# design-v1_1.net
KiCad netlist of a schematic drawn in EAGLE
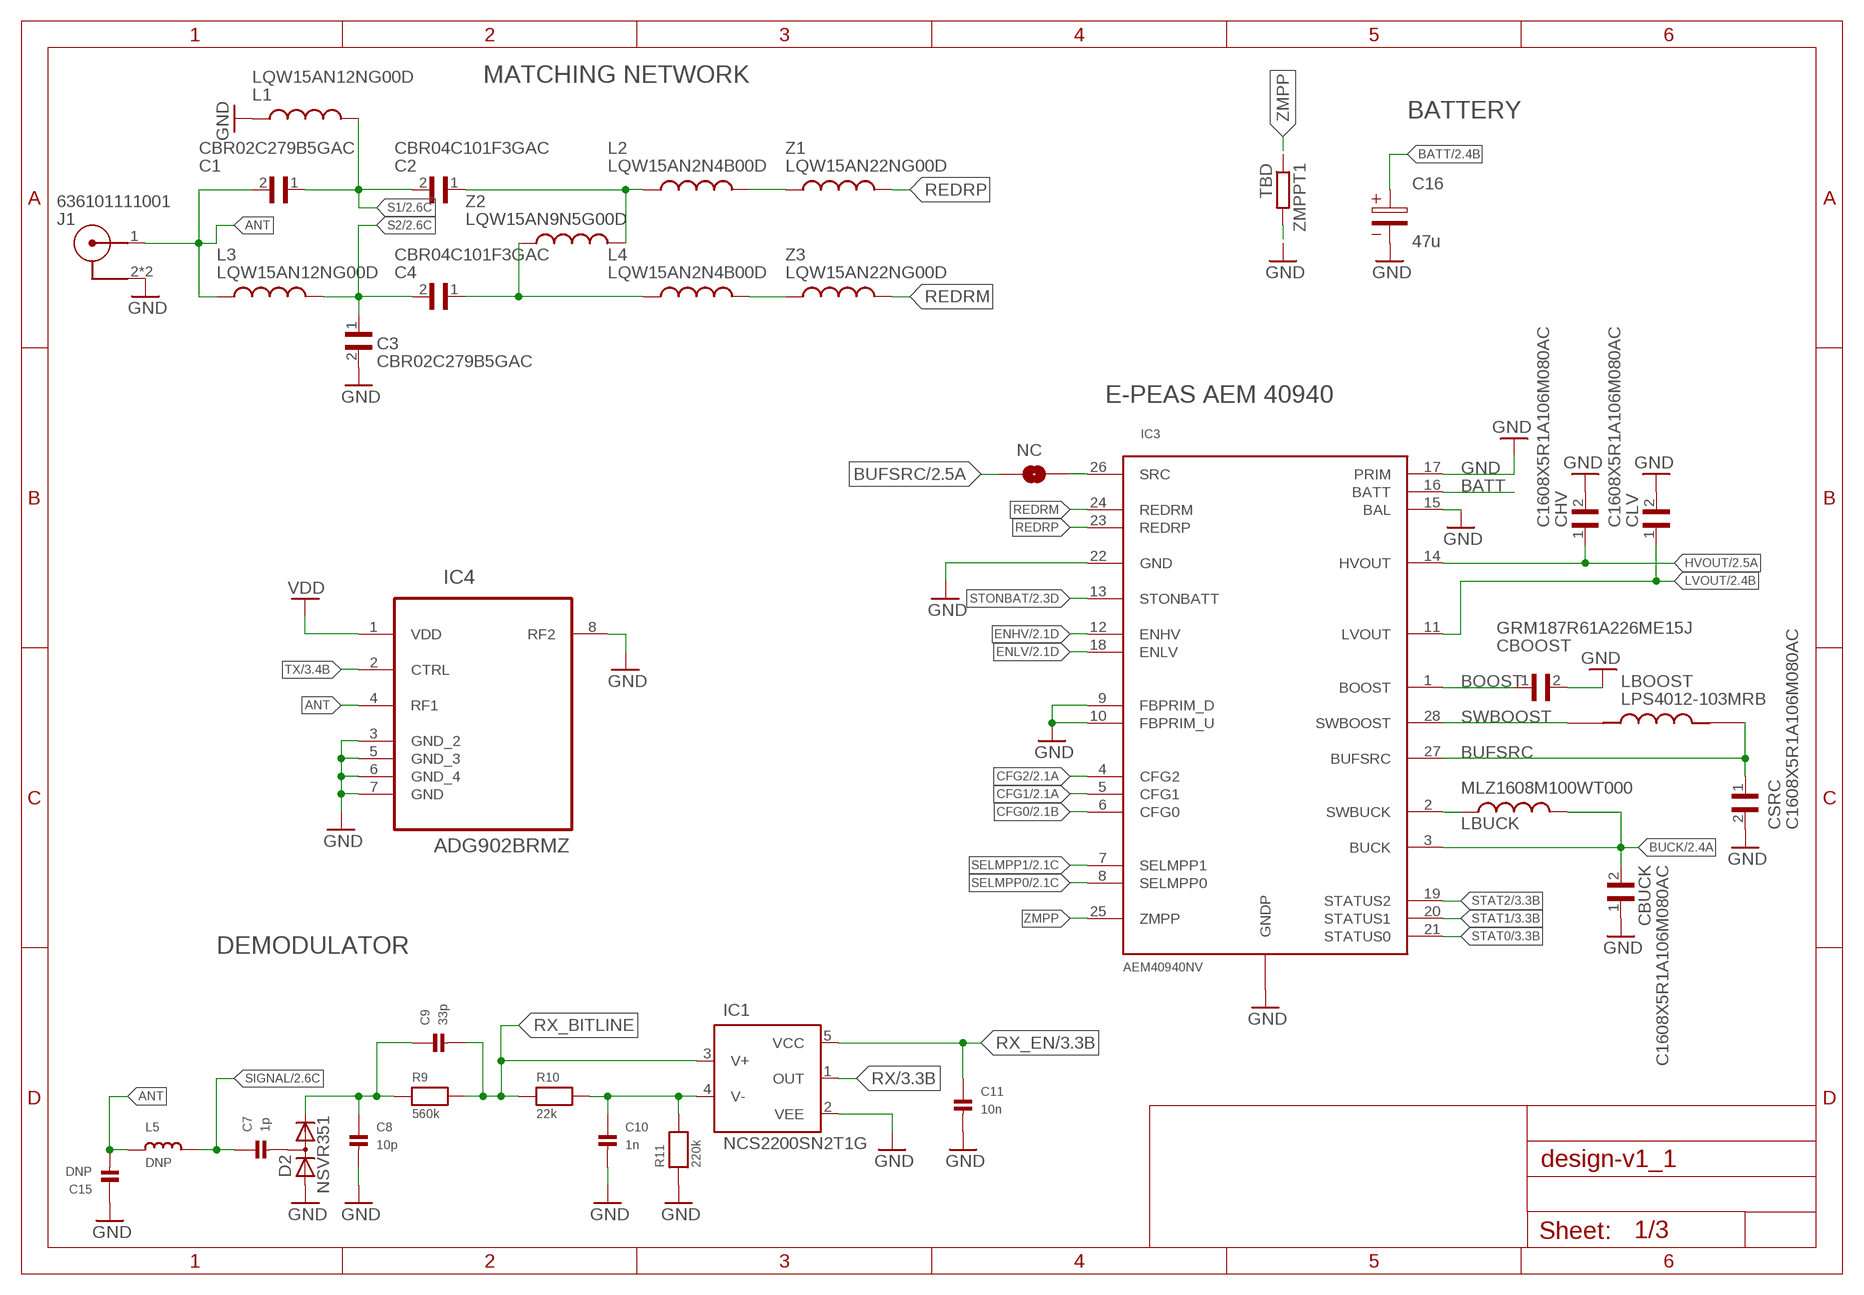
[diagram p0: schematic, sheet 1]
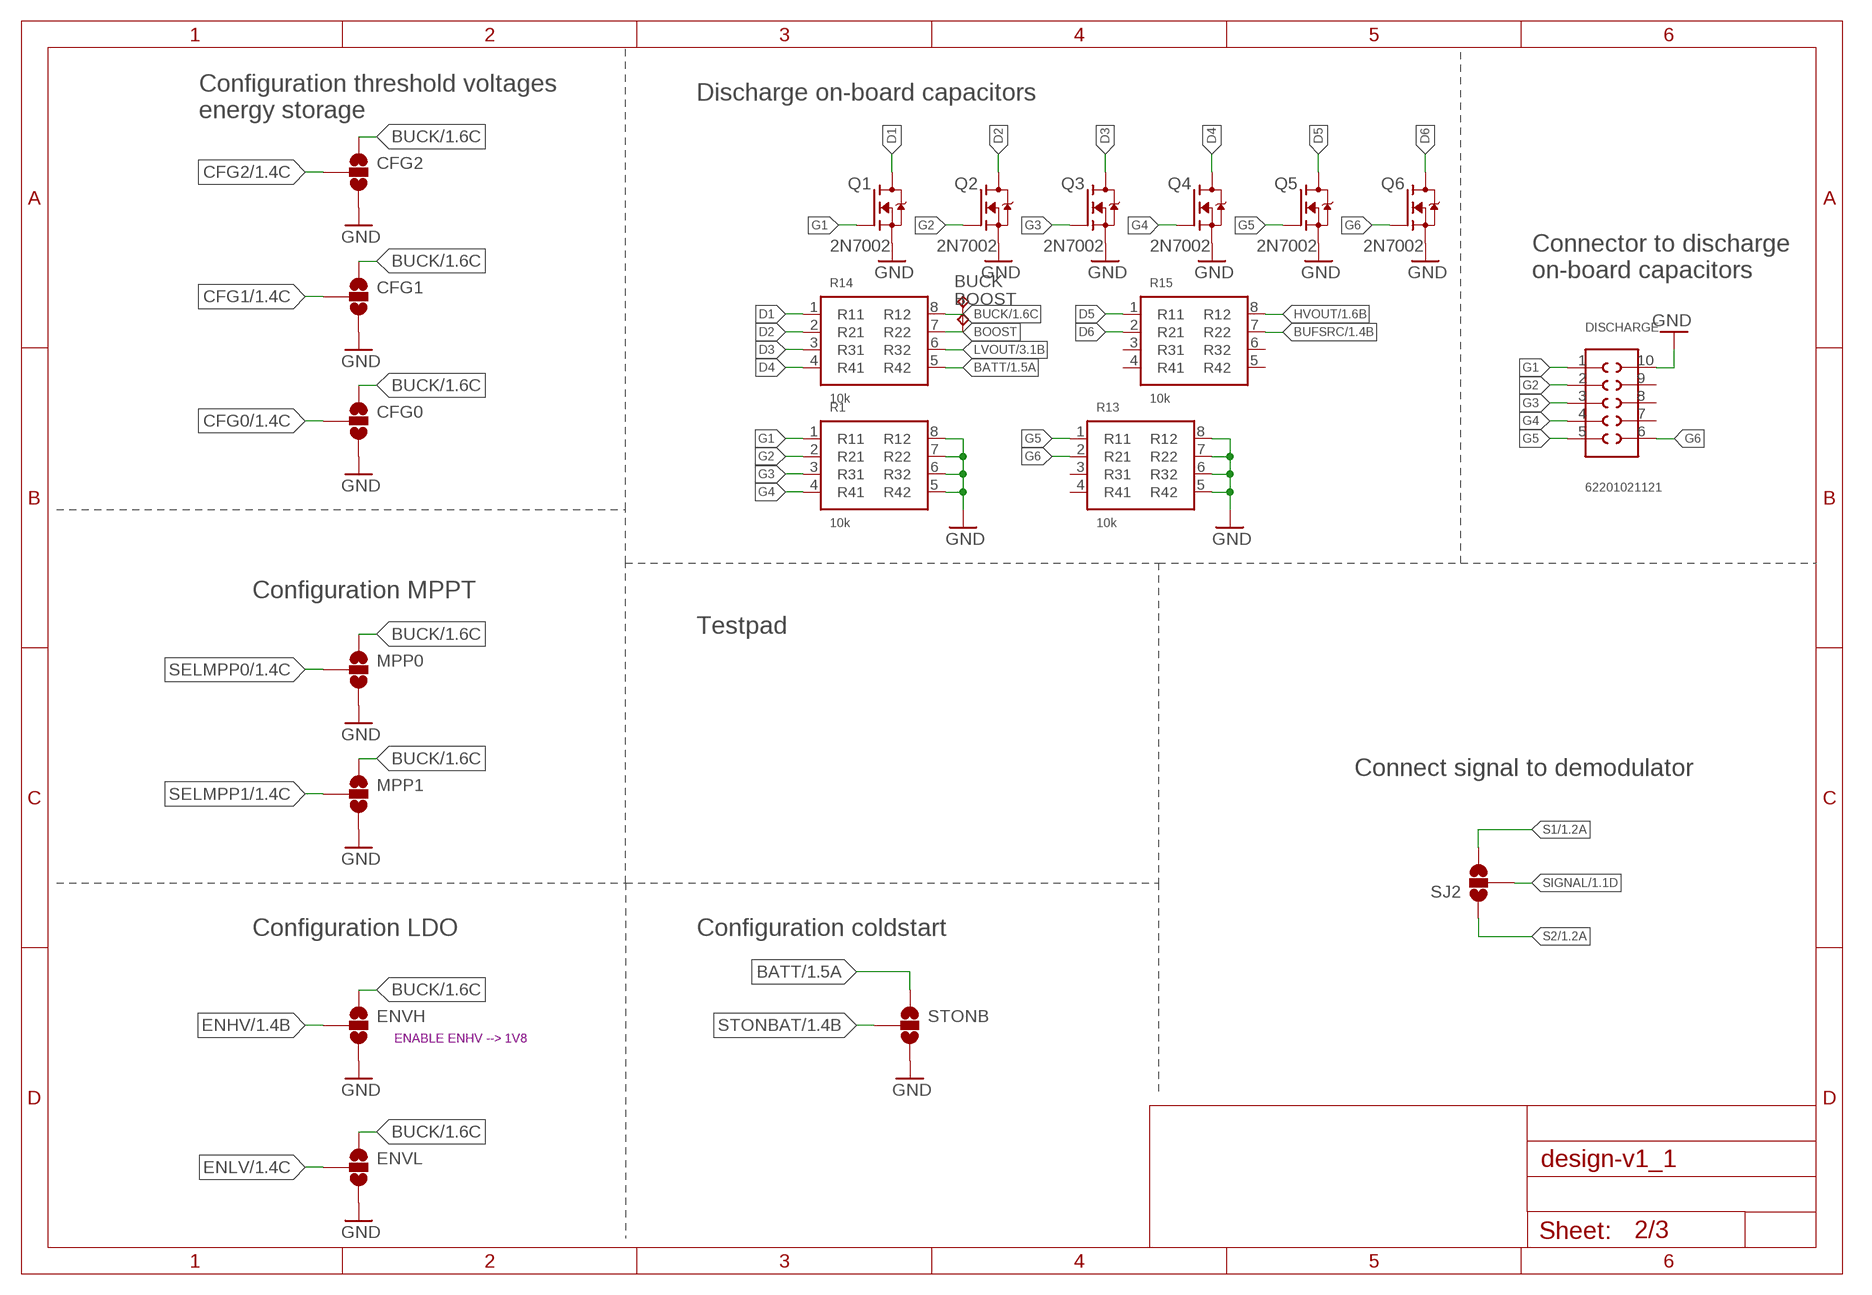
[diagram p1: schematic, sheet 2]
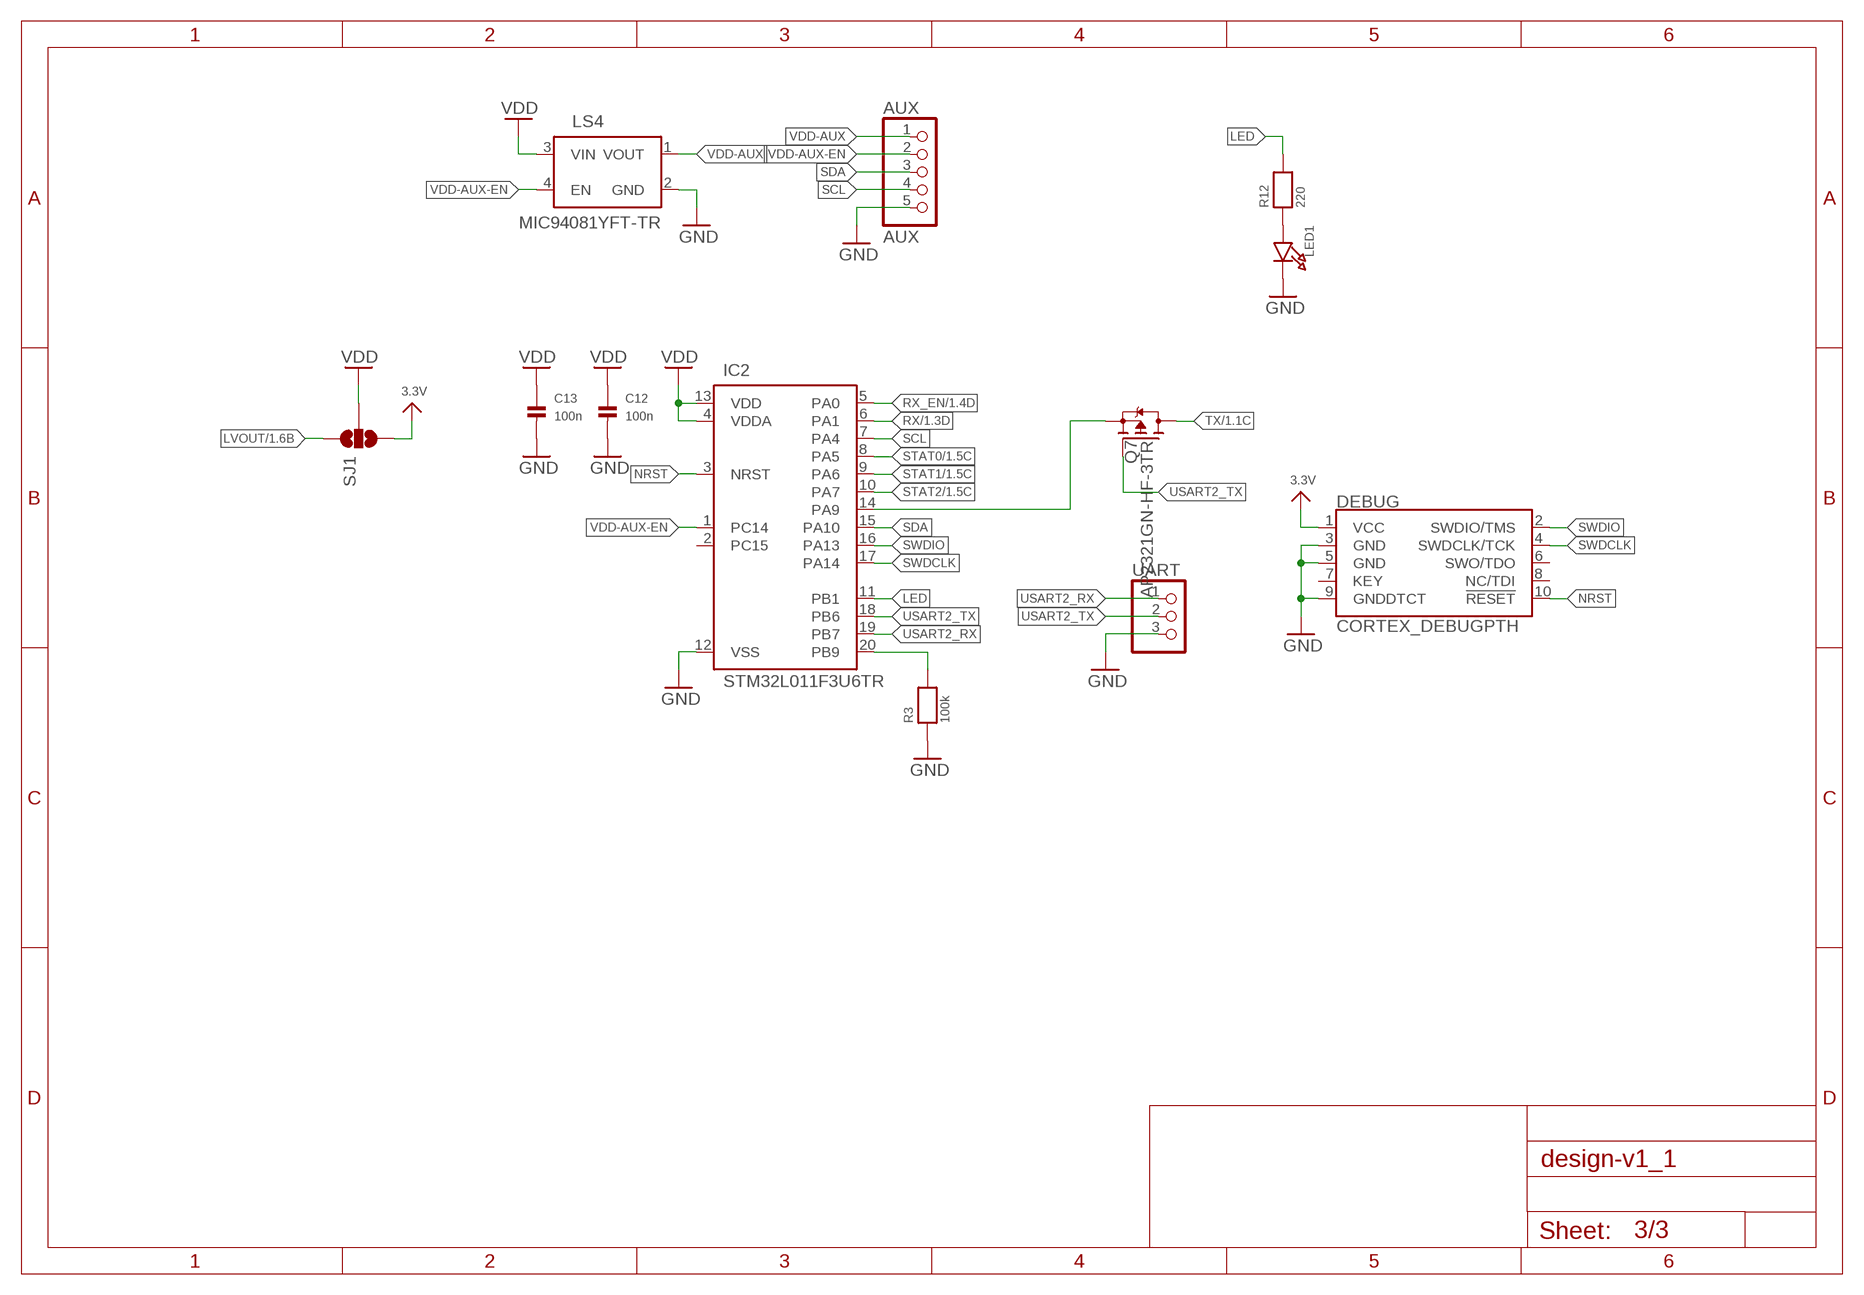
[diagram p2: schematic, sheet 3]

(export (version "E")
  (design (tool "Eeschema 10.0.6"))
  (components
    (comp (ref "BOOST")
      (value "TPTP06R")
      (footprint "eagle-import:TP06R")
      (libsource (lib "eagle-import") (part "TPTP06R"))
    )
    (comp (ref "BUCK")
      (value "TPTP06R")
      (footprint "eagle-import:TP06R")
      (libsource (lib "eagle-import") (part "TPTP06R"))
    )
    (comp (ref "CFG0")
      (value "JUMPER-SMT_3_NO_SILK")
      (footprint "eagle-import:SMT-JUMPER_3_NO_SILK")
      (libsource (lib "eagle-import") (part "JUMPER-SMT_3_NO_SILK"))
    )
    (comp (ref "CFG1")
      (value "JUMPER-SMT_3_NO_SILK")
      (footprint "eagle-import:SMT-JUMPER_3_NO_SILK")
      (libsource (lib "eagle-import") (part "JUMPER-SMT_3_NO_SILK"))
    )
    (comp (ref "CFG2")
      (value "JUMPER-SMT_3_NO_SILK")
      (footprint "eagle-import:SMT-JUMPER_3_NO_SILK")
      (libsource (lib "eagle-import") (part "JUMPER-SMT_3_NO_SILK"))
    )
    (comp (ref "DISCHARGE")
      (value "62201021121")
      (footprint "eagle-import:62201021121")
      (libsource (lib "eagle-import") (part "62201021121"))
    )
    (comp (ref "ENVH")
      (value "JUMPER-SMT_3_NO_SILK")
      (footprint "eagle-import:SMT-JUMPER_3_NO_SILK")
      (libsource (lib "eagle-import") (part "JUMPER-SMT_3_NO_SILK"))
    )
    (comp (ref "ENVL")
      (value "JUMPER-SMT_3_NO_SILK")
      (footprint "eagle-import:SMT-JUMPER_3_NO_SILK")
      (libsource (lib "eagle-import") (part "JUMPER-SMT_3_NO_SILK"))
    )
    (comp (ref "MPP0")
      (value "JUMPER-SMT_3_NO_SILK")
      (footprint "eagle-import:SMT-JUMPER_3_NO_SILK")
      (libsource (lib "eagle-import") (part "JUMPER-SMT_3_NO_SILK"))
    )
    (comp (ref "MPP1")
      (value "JUMPER-SMT_3_NO_SILK")
      (footprint "eagle-import:SMT-JUMPER_3_NO_SILK")
      (libsource (lib "eagle-import") (part "JUMPER-SMT_3_NO_SILK"))
    )
    (comp (ref "Q1")
      (value "2N7002")
      (footprint "eagle-import:SOT95P240X111-3N")
      (fields (field (name "MF") "ON Semiconductor"))
      (libsource (lib "eagle-import") (part "2N7002"))
    )
    (comp (ref "Q2")
      (value "2N7002")
      (footprint "eagle-import:SOT95P240X111-3N")
      (fields (field (name "MF") "ON Semiconductor"))
      (libsource (lib "eagle-import") (part "2N7002"))
    )
    (comp (ref "Q3")
      (value "2N7002")
      (footprint "eagle-import:SOT95P240X111-3N")
      (fields (field (name "MF") "ON Semiconductor"))
      (libsource (lib "eagle-import") (part "2N7002"))
    )
    (comp (ref "Q4")
      (value "2N7002")
      (footprint "eagle-import:SOT95P240X111-3N")
      (fields (field (name "MF") "ON Semiconductor"))
      (libsource (lib "eagle-import") (part "2N7002"))
    )
    (comp (ref "Q5")
      (value "2N7002")
      (footprint "eagle-import:SOT95P240X111-3N")
      (fields (field (name "MF") "ON Semiconductor"))
      (libsource (lib "eagle-import") (part "2N7002"))
    )
    (comp (ref "Q6")
      (value "2N7002")
      (footprint "eagle-import:SOT95P240X111-3N")
      (fields (field (name "MF") "ON Semiconductor"))
      (libsource (lib "eagle-import") (part "2N7002"))
    )
    (comp (ref "R1")
      (value "10k")
      (footprint "eagle-import:RESCAXS50P200X100X45-8N")
      (libsource (lib "eagle-import") (part "CAY10"))
    )
    (comp (ref "R13")
      (value "10k")
      (footprint "eagle-import:RESCAXS50P200X100X45-8N")
      (libsource (lib "eagle-import") (part "CAY10"))
    )
    (comp (ref "R14")
      (value "10k")
      (footprint "eagle-import:RESCAXS50P200X100X45-8N")
      (libsource (lib "eagle-import") (part "CAY10"))
    )
    (comp (ref "R15")
      (value "10k")
      (footprint "eagle-import:RESCAXS50P200X100X45-8N")
      (libsource (lib "eagle-import") (part "CAY10"))
    )
    (comp (ref "SJ2")
      (value "SOLDERJUMPER_2WAYS")
      (footprint "eagle-import:SJ_3")
      (libsource (lib "eagle-import") (part "SOLDERJUMPER_2WAYS"))
    )
    (comp (ref "STONB")
      (value "JUMPER-SMT_3_NO_SILK")
      (footprint "eagle-import:SMT-JUMPER_3_NO_SILK")
      (libsource (lib "eagle-import") (part "JUMPER-SMT_3_NO_SILK"))
    )
    (comp (ref "AUX")
      (value "AUX")
      (footprint "eagle-import:1X05_ROUND")
      (libsource (lib "eagle-import") (part "HEADER-1X5ROUND"))
    )
    (comp (ref "C12")
      (value "100n")
      (footprint "eagle-import:0402")
      (libsource (lib "eagle-import") (part "CAP_CERAMIC0402"))
    )
    (comp (ref "C13")
      (value "100n")
      (footprint "eagle-import:0402")
      (libsource (lib "eagle-import") (part "CAP_CERAMIC0402"))
    )
    (comp (ref "DEBUG")
      (value "CORTEX_DEBUGPTH")
      (footprint "eagle-import:2X5-PTH-1.27MM")
      (libsource (lib "eagle-import") (part "CORTEX_DEBUGPTH"))
    )
    (comp (ref "IC2")
      (value "STM32L011F3U6TR")
      (footprint "eagle-import:QFN50P300X300X60-21N")
      (fields (field (name "MANUFACTURER") "STMicroelectronics"))
      (libsource (lib "eagle-import") (part "STM32L011F3U6TR"))
    )
    (comp (ref "LED1")
      (value "LED0805")
      (footprint "eagle-import:CHIPLED_0805")
      (libsource (lib "eagle-import") (part "LED0805"))
    )
    (comp (ref "LS4")
      (value "MIC94081YFT-TR")
      (footprint "eagle-import:IC_MIC94081YFT-TR")
      (fields (field (name "MF") "Microchip"))
      (libsource (lib "eagle-import") (part "MIC94081YFT-TR"))
    )
    (comp (ref "Q7")
      (value "AP2321GN-HF-3TR")
      (footprint "eagle-import:SOT23-3")
      (fields (field (name "MF") "Advanced Power Electronics"))
      (libsource (lib "eagle-import") (part "AP2321GN-HF-3TR"))
    )
    (comp (ref "R3")
      (value "100k")
      (footprint "eagle-import:0402")
      (libsource (lib "eagle-import") (part "RESISTOR0402"))
    )
    (comp (ref "R12")
      (value "220")
      (footprint "eagle-import:0603")
      (libsource (lib "eagle-import") (part "RESISTOR0603"))
    )
    (comp (ref "SJ1")
      (value "SOLDERJUMPER_2WAYS")
      (footprint "eagle-import:SJ_3")
      (libsource (lib "eagle-import") (part "SOLDERJUMPER_2WAYS"))
    )
    (comp (ref "UART")
      (value "HEADER-1X3ROUND")
      (footprint "eagle-import:1X03_ROUND")
      (libsource (lib "eagle-import") (part "HEADER-1X3ROUND"))
    )
    (comp (ref "C1")
      (value "CBR02C279B5GAC")
      (footprint "eagle-import:CAPC1005X55N")
      (fields (field (name "MF") "KEMET") (field (name "MP") "CBR04C101F3GAC"))
      (libsource (lib "eagle-import") (part "CBR04C101F3GAC"))
    )
    (comp (ref "C2")
      (value "CBR04C101F3GAC")
      (footprint "eagle-import:CAPC1005X55N")
      (fields (field (name "MF") "KEMET"))
      (libsource (lib "eagle-import") (part "CBR04C101F3GAC"))
    )
    (comp (ref "C3")
      (value "CBR02C279B5GAC")
      (footprint "eagle-import:CAPC1005X55N")
      (fields (field (name "MF") "KEMET") (field (name "MP") "CBR04C101F3GAC"))
      (libsource (lib "eagle-import") (part "CBR04C101F3GAC"))
    )
    (comp (ref "C4")
      (value "CBR04C101F3GAC")
      (footprint "eagle-import:CAPC1005X55N")
      (fields (field (name "MF") "KEMET"))
      (libsource (lib "eagle-import") (part "CBR04C101F3GAC"))
    )
    (comp (ref "C7")
      (value "1p")
      (footprint "eagle-import:0402")
      (libsource (lib "eagle-import") (part "CAP_CERAMIC0402"))
    )
    (comp (ref "C8")
      (value "10p")
      (footprint "eagle-import:0402")
      (libsource (lib "eagle-import") (part "CAP_CERAMIC0402"))
    )
    (comp (ref "C9")
      (value "33p")
      (footprint "eagle-import:0402")
      (libsource (lib "eagle-import") (part "CAP_CERAMIC0402"))
    )
    (comp (ref "C10")
      (value "1n")
      (footprint "eagle-import:0402")
      (libsource (lib "eagle-import") (part "CAP_CERAMIC0402"))
    )
    (comp (ref "C11")
      (value "10n")
      (footprint "eagle-import:0402")
      (libsource (lib "eagle-import") (part "CAP_CERAMIC0402"))
    )
    (comp (ref "C15")
      (value "DNP")
      (footprint "eagle-import:0402")
      (libsource (lib "eagle-import") (part "CAP_CERAMIC0402"))
    )
    (comp (ref "C16")
      (value "47u")
      (footprint "eagle-import:3X1.6X1.4(BXCXA)")
      (libsource (lib "eagle-import") (part "WCAP-ASLI_865080242004_5X5,5"))
    )
    (comp (ref "CBOOST")
      (value "GRM187R61A226ME15J")
      (footprint "eagle-import:CAPC1608X80N")
      (fields (field (name "MF") "Murata Electronics"))
      (libsource (lib "eagle-import") (part "GRM187R61A226ME15J"))
    )
    (comp (ref "CBUCK")
      (value "C1608X5R1A106M080AC")
      (footprint "eagle-import:CAPC1608X90N")
      (fields (field (name "MF") "TDK"))
      (libsource (lib "eagle-import") (part "C1608X5R1A106M080AC"))
    )
    (comp (ref "CHV")
      (value "C1608X5R1A106M080AC")
      (footprint "eagle-import:CAPC1608X90N")
      (fields (field (name "MF") "TDK"))
      (libsource (lib "eagle-import") (part "C1608X5R1A106M080AC"))
    )
    (comp (ref "CLV")
      (value "C1608X5R1A106M080AC")
      (footprint "eagle-import:CAPC1608X90N")
      (fields (field (name "MF") "TDK"))
      (libsource (lib "eagle-import") (part "C1608X5R1A106M080AC"))
    )
    (comp (ref "CSRC")
      (value "C1608X5R1A106M080AC")
      (footprint "eagle-import:CAPC1608X90N")
      (fields (field (name "MF") "TDK"))
      (libsource (lib "eagle-import") (part "C1608X5R1A106M080AC"))
    )
    (comp (ref "D2")
      (value "NSVR351")
      (footprint "eagle-import:SOT23")
      (libsource (lib "eagle-import") (part "DIODE_2CACA-SOT23"))
    )
    (comp (ref "IC1")
      (value "NCS2200SN2T1G")
      (footprint "eagle-import:SOT95P275X110-5N")
      (libsource (lib "eagle-import") (part "NCS2200"))
    )
    (comp (ref "IC3")
      (value "AEM40940NV")
      (footprint "eagle-import:QFN28_5X5_05P_NO_VIAS")
      (fields (field (name "MF") "Sensata") (field (name "MP") "AEM40940"))
      (libsource (lib "eagle-import") (part "AEM40940NV"))
    )
    (comp (ref "IC4")
      (value "ADG902BRMZ")
      (footprint "eagle-import:SOP65P490X110-8N")
      (fields (field (name "MF") "Analog Devices"))
      (libsource (lib "eagle-import") (part "ADG902BRMZ"))
    )
    (comp (ref "J1")
      (value "636101111001")
      (footprint "eagle-import:636101111001")
      (libsource (lib "eagle-import") (part "636101111001"))
    )
    (comp (ref "L1")
      (value "LQW15AN12NG00D")
      (footprint "eagle-import:INDC1006X60N")
      (fields (field (name "MF") "Murata"))
      (libsource (lib "eagle-import") (part "LQW15AN12NG00D"))
    )
    (comp (ref "L2")
      (value "LQW15AN2N4B00D")
      (footprint "eagle-import:INDC1006X60N")
      (fields (field (name "MF") "Murata"))
      (libsource (lib "eagle-import") (part "LQW15AN2N4B00D"))
    )
    (comp (ref "L3")
      (value "LQW15AN12NG00D")
      (footprint "eagle-import:INDC1006X60N")
      (fields (field (name "MF") "Murata"))
      (libsource (lib "eagle-import") (part "LQW15AN12NG00D"))
    )
    (comp (ref "L4")
      (value "LQW15AN2N4B00D")
      (footprint "eagle-import:INDC1006X60N")
      (fields (field (name "MF") "Murata"))
      (libsource (lib "eagle-import") (part "LQW15AN2N4B00D"))
    )
    (comp (ref "L5")
      (value "DNP")
      (footprint "eagle-import:_0402")
      (libsource (lib "eagle-import") (part "INDUCTOR_0402"))
    )
    (comp (ref "LBOOST")
      (value "LPS4012-103MRB")
      (footprint "eagle-import:IND_LPS4012-103MRB")
      (fields (field (name "MF") "Coilcraft"))
      (libsource (lib "eagle-import") (part "LPS4012-103MRB"))
    )
    (comp (ref "LBUCK")
      (value "MLZ1608M100WT000")
      (footprint "eagle-import:INDC1608X95N")
      (libsource (lib "eagle-import") (part "MLZ1608M100WT000"))
    )
    (comp (ref "NC")
      (value "JUMPER-SMT_2_NO_SILK")
      (footprint "eagle-import:SMT-JUMPER_2_NO_SILK")
      (libsource (lib "eagle-import") (part "JUMPER-SMT_2_NO_SILK"))
    )
    (comp (ref "R9")
      (value "560k")
      (footprint "eagle-import:0402")
      (libsource (lib "eagle-import") (part "RESISTOR0402"))
    )
    (comp (ref "R10")
      (value "22k")
      (footprint "eagle-import:0402")
      (libsource (lib "eagle-import") (part "RESISTOR0402"))
    )
    (comp (ref "R11")
      (value "220k")
      (footprint "eagle-import:0402")
      (libsource (lib "eagle-import") (part "RESISTOR0402"))
    )
    (comp (ref "Z1")
      (value "LQW15AN22NG00D")
      (footprint "eagle-import:INDC1006X60N")
      (fields (field (name "MF") "Murata"))
      (libsource (lib "eagle-import") (part "LQW15AN22NG00D"))
    )
    (comp (ref "Z2")
      (value "LQW15AN9N5G00D")
      (footprint "eagle-import:INDC1006X60N")
      (fields (field (name "MF") "Murata"))
      (libsource (lib "eagle-import") (part "LQW15AN9N5G00D"))
    )
    (comp (ref "Z3")
      (value "LQW15AN22NG00D")
      (footprint "eagle-import:INDC1006X60N")
      (fields (field (name "MF") "Murata"))
      (libsource (lib "eagle-import") (part "LQW15AN22NG00D"))
    )
    (comp (ref "ZMPPT1")
      (value "TBD")
      (footprint "eagle-import:R0805")
      (libsource (lib "eagle-import") (part "R-EU_R0805"))
    )
  )
  (nets
    (net (code "1") (name "3.3V") (class "Default")
      (node (ref "DEBUG") (pin "1") (pinfunction "VCC_1") (pintype "bidirectional"))
      (node (ref "SJ1") (pin "3") (pinfunction "3_3") (pintype "passive"))
    )
    (net (code "2") (name "ANT") (class "Default")
      (node (ref "C1") (pin "2") (pinfunction "2_2") (pintype "passive"))
      (node (ref "C15") (pin "2") (pinfunction "P$2_2") (pintype "passive"))
      (node (ref "IC4") (pin "4") (pinfunction "RF1_4") (pintype "passive"))
      (node (ref "J1") (pin "1") (pinfunction "1_1") (pintype "passive"))
      (node (ref "L3") (pin "1") (pinfunction "1_1") (pintype "passive"))
      (node (ref "L5") (pin "1") (pinfunction "1_1") (pintype "passive"))
    )
    (net (code "3") (name "BATT") (class "Default")
      (node (ref "C16") (pin "1") (pinfunction "1_1") (pintype "passive"))
      (node (ref "IC3") (pin "16") (pinfunction "BATT_16") (pintype "bidirectional"))
      (node (ref "R14") (pin "5") (pinfunction "R42_5") (pintype "bidirectional"))
      (node (ref "STONB") (pin "1") (pinfunction "1_1") (pintype "passive"))
    )
    (net (code "4") (name "BOOST") (class "Default")
      (node (ref "BOOST") (pin "TP") (pinfunction "TP_TP") (pintype "input"))
      (node (ref "CBOOST") (pin "1") (pinfunction "1_1") (pintype "passive"))
      (node (ref "IC3") (pin "1") (pinfunction "BOOST_1") (pintype "bidirectional"))
      (node (ref "R14") (pin "7") (pinfunction "R22_7") (pintype "bidirectional"))
    )
    (net (code "5") (name "BUCK") (class "Default")
      (node (ref "BUCK") (pin "TP") (pinfunction "TP_TP") (pintype "input"))
      (node (ref "CBUCK") (pin "2") (pinfunction "2_2") (pintype "passive"))
      (node (ref "CFG0") (pin "1") (pinfunction "1_1") (pintype "passive"))
      (node (ref "CFG1") (pin "1") (pinfunction "1_1") (pintype "passive"))
      (node (ref "CFG2") (pin "1") (pinfunction "1_1") (pintype "passive"))
      (node (ref "ENVH") (pin "1") (pinfunction "1_1") (pintype "passive"))
      (node (ref "ENVL") (pin "1") (pinfunction "1_1") (pintype "passive"))
      (node (ref "IC3") (pin "3") (pinfunction "BUCK_3") (pintype "bidirectional"))
      (node (ref "LBUCK") (pin "2") (pinfunction "2_2") (pintype "passive"))
      (node (ref "MPP0") (pin "1") (pinfunction "1_1") (pintype "passive"))
      (node (ref "MPP1") (pin "1") (pinfunction "1_1") (pintype "passive"))
      (node (ref "R14") (pin "8") (pinfunction "R12_8") (pintype "bidirectional"))
    )
    (net (code "6") (name "BUFSRC") (class "Default")
      (node (ref "CSRC") (pin "1") (pinfunction "1_1") (pintype "passive"))
      (node (ref "IC3") (pin "27") (pinfunction "BUFSRC_27") (pintype "bidirectional"))
      (node (ref "LBOOST") (pin "2") (pinfunction "2_2") (pintype "passive"))
      (node (ref "NC") (pin "2") (pinfunction "2_2") (pintype "passive"))
      (node (ref "R15") (pin "7") (pinfunction "R22_7") (pintype "bidirectional"))
    )
    (net (code "7") (name "CFG0") (class "Default")
      (node (ref "CFG0") (pin "2") (pinfunction "2_2") (pintype "passive"))
      (node (ref "IC3") (pin "6") (pinfunction "CFG0_6") (pintype "input"))
    )
    (net (code "8") (name "CFG1") (class "Default")
      (node (ref "CFG1") (pin "2") (pinfunction "2_2") (pintype "passive"))
      (node (ref "IC3") (pin "5") (pinfunction "CFG1_5") (pintype "input"))
    )
    (net (code "9") (name "CFG2") (class "Default")
      (node (ref "CFG2") (pin "2") (pinfunction "2_2") (pintype "passive"))
      (node (ref "IC3") (pin "4") (pinfunction "CFG2_4") (pintype "input"))
    )
    (net (code "10") (name "D1") (class "Default")
      (node (ref "Q1") (pin "3") (pinfunction "D_3") (pintype "passive"))
      (node (ref "R14") (pin "1") (pinfunction "R11_1") (pintype "bidirectional"))
    )
    (net (code "11") (name "D2") (class "Default")
      (node (ref "Q2") (pin "3") (pinfunction "D_3") (pintype "passive"))
      (node (ref "R14") (pin "2") (pinfunction "R21_2") (pintype "bidirectional"))
    )
    (net (code "12") (name "D3") (class "Default")
      (node (ref "Q3") (pin "3") (pinfunction "D_3") (pintype "passive"))
      (node (ref "R14") (pin "3") (pinfunction "R31_3") (pintype "bidirectional"))
    )
    (net (code "13") (name "D4") (class "Default")
      (node (ref "Q4") (pin "3") (pinfunction "D_3") (pintype "passive"))
      (node (ref "R14") (pin "4") (pinfunction "R41_4") (pintype "bidirectional"))
    )
    (net (code "14") (name "D5") (class "Default")
      (node (ref "Q5") (pin "3") (pinfunction "D_3") (pintype "passive"))
      (node (ref "R15") (pin "1") (pinfunction "R11_1") (pintype "bidirectional"))
    )
    (net (code "15") (name "D6") (class "Default")
      (node (ref "Q6") (pin "3") (pinfunction "D_3") (pintype "passive"))
      (node (ref "R15") (pin "2") (pinfunction "R21_2") (pintype "bidirectional"))
    )
    (net (code "16") (name "ENHV") (class "Default")
      (node (ref "ENVH") (pin "2") (pinfunction "2_2") (pintype "passive"))
      (node (ref "IC3") (pin "12") (pinfunction "ENHV_12") (pintype "input"))
    )
    (net (code "17") (name "ENLV") (class "Default")
      (node (ref "ENVL") (pin "2") (pinfunction "2_2") (pintype "passive"))
      (node (ref "IC3") (pin "18") (pinfunction "ENLV_18") (pintype "input"))
    )
    (net (code "18") (name "G1") (class "Default")
      (node (ref "DISCHARGE") (pin "1") (pinfunction "1_1") (pintype "passive"))
      (node (ref "Q1") (pin "1") (pinfunction "G_1") (pintype "passive"))
      (node (ref "R1") (pin "1") (pinfunction "R11_1") (pintype "bidirectional"))
    )
    (net (code "19") (name "G2") (class "Default")
      (node (ref "DISCHARGE") (pin "2") (pinfunction "2_2") (pintype "passive"))
      (node (ref "Q2") (pin "1") (pinfunction "G_1") (pintype "passive"))
      (node (ref "R1") (pin "2") (pinfunction "R21_2") (pintype "bidirectional"))
    )
    (net (code "20") (name "G3") (class "Default")
      (node (ref "DISCHARGE") (pin "3") (pinfunction "3_3") (pintype "passive"))
      (node (ref "Q3") (pin "1") (pinfunction "G_1") (pintype "passive"))
      (node (ref "R1") (pin "3") (pinfunction "R31_3") (pintype "bidirectional"))
    )
    (net (code "21") (name "G4") (class "Default")
      (node (ref "DISCHARGE") (pin "4") (pinfunction "4_4") (pintype "passive"))
      (node (ref "Q4") (pin "1") (pinfunction "G_1") (pintype "passive"))
      (node (ref "R1") (pin "4") (pinfunction "R41_4") (pintype "bidirectional"))
    )
    (net (code "22") (name "G5") (class "Default")
      (node (ref "DISCHARGE") (pin "5") (pinfunction "5_5") (pintype "passive"))
      (node (ref "Q5") (pin "1") (pinfunction "G_1") (pintype "passive"))
      (node (ref "R13") (pin "1") (pinfunction "R11_1") (pintype "bidirectional"))
    )
    (net (code "23") (name "G6") (class "Default")
      (node (ref "DISCHARGE") (pin "6") (pinfunction "6_6") (pintype "passive"))
      (node (ref "Q6") (pin "1") (pinfunction "G_1") (pintype "passive"))
      (node (ref "R13") (pin "2") (pinfunction "R21_2") (pintype "bidirectional"))
    )
    (net (code "24") (name "GND") (class "Default")
      (node (ref "AUX") (pin "5") (pinfunction "5_5") (pintype "passive"))
      (node (ref "C10") (pin "2") (pinfunction "P$2_2") (pintype "passive"))
      (node (ref "C11") (pin "2") (pinfunction "P$2_2") (pintype "passive"))
      (node (ref "C12") (pin "2") (pinfunction "P$2_2") (pintype "passive"))
      (node (ref "C13") (pin "2") (pinfunction "P$2_2") (pintype "passive"))
      (node (ref "C15") (pin "1") (pinfunction "P$1_1") (pintype "passive"))
      (node (ref "C16") (pin "2") (pinfunction "2_2") (pintype "passive"))
      (node (ref "C3") (pin "2") (pinfunction "2_2") (pintype "passive"))
      (node (ref "C8") (pin "2") (pinfunction "P$2_2") (pintype "passive"))
      (node (ref "CBOOST") (pin "2") (pinfunction "2_2") (pintype "passive"))
      (node (ref "CBUCK") (pin "1") (pinfunction "1_1") (pintype "passive"))
      (node (ref "CFG0") (pin "3") (pinfunction "3_3") (pintype "passive"))
      (node (ref "CFG1") (pin "3") (pinfunction "3_3") (pintype "passive"))
      (node (ref "CFG2") (pin "3") (pinfunction "3_3") (pintype "passive"))
      (node (ref "CHV") (pin "2") (pinfunction "2_2") (pintype "passive"))
      (node (ref "CLV") (pin "2") (pinfunction "2_2") (pintype "passive"))
      (node (ref "CSRC") (pin "2") (pinfunction "2_2") (pintype "passive"))
      (node (ref "D2") (pin "1") (pinfunction "A_1") (pintype "passive"))
      (node (ref "DEBUG") (pin "3") (pinfunction "GND_3") (pintype "bidirectional"))
      (node (ref "DEBUG") (pin "5") (pinfunction "GND_5") (pintype "bidirectional"))
      (node (ref "DEBUG") (pin "9") (pinfunction "GNDDTCT_9") (pintype "bidirectional"))
      (node (ref "DISCHARGE") (pin "10") (pinfunction "10_10") (pintype "passive"))
      (node (ref "ENVH") (pin "3") (pinfunction "3_3") (pintype "passive"))
      (node (ref "ENVL") (pin "3") (pinfunction "3_3") (pintype "passive"))
      (node (ref "IC1") (pin "2") (pinfunction "VEE_2") (pintype "bidirectional"))
      (node (ref "IC2") (pin "12") (pinfunction "VSS_12") (pintype "bidirectional"))
      (node (ref "IC3") (pin "10") (pinfunction "FBPRIM_U_10") (pintype "bidirectional"))
      (node (ref "IC3") (pin "15") (pinfunction "BAL_15") (pintype "bidirectional"))
      (node (ref "IC3") (pin "17") (pinfunction "PRIM_17") (pintype "bidirectional"))
      (node (ref "IC3") (pin "22") (pinfunction "GND_22") (pintype "bidirectional"))
      (node (ref "IC3") (pin "9") (pinfunction "FBPRIM_D_9") (pintype "bidirectional"))
      (node (ref "IC3") (pin "GND") (pinfunction "GNDP_GND") (pintype "power_in"))
      (node (ref "IC4") (pin "3") (pinfunction "GND_2_3") (pintype "passive"))
      (node (ref "IC4") (pin "5") (pinfunction "GND_3_5") (pintype "passive"))
      (node (ref "IC4") (pin "6") (pinfunction "GND_4_6") (pintype "passive"))
      (node (ref "IC4") (pin "7") (pinfunction "GND_7") (pintype "passive"))
      (node (ref "IC4") (pin "8") (pinfunction "RF2_8") (pintype "passive"))
      (node (ref "J1") (pin "2") (pinfunction "2_2") (pintype "passive"))
      (node (ref "J1") (pin "3") (pinfunction "2_3") (pintype "passive"))
      (node (ref "L1") (pin "1") (pinfunction "1_1") (pintype "passive"))
      (node (ref "LED1") (pin "C") (pinfunction "C_C") (pintype "passive"))
      (node (ref "LS4") (pin "2") (pinfunction "GND_2") (pintype "power_in"))
      (node (ref "MPP0") (pin "3") (pinfunction "3_3") (pintype "passive"))
      (node (ref "MPP1") (pin "3") (pinfunction "3_3") (pintype "passive"))
      (node (ref "Q1") (pin "2") (pinfunction "S_2") (pintype "passive"))
      (node (ref "Q2") (pin "2") (pinfunction "S_2") (pintype "passive"))
      (node (ref "Q3") (pin "2") (pinfunction "S_2") (pintype "passive"))
      (node (ref "Q4") (pin "2") (pinfunction "S_2") (pintype "passive"))
      (node (ref "Q5") (pin "2") (pinfunction "S_2") (pintype "passive"))
      (node (ref "Q6") (pin "2") (pinfunction "S_2") (pintype "passive"))
      (node (ref "R1") (pin "5") (pinfunction "R42_5") (pintype "bidirectional"))
      (node (ref "R1") (pin "6") (pinfunction "R32_6") (pintype "bidirectional"))
      (node (ref "R1") (pin "7") (pinfunction "R22_7") (pintype "bidirectional"))
      (node (ref "R1") (pin "8") (pinfunction "R12_8") (pintype "bidirectional"))
      (node (ref "R11") (pin "1") (pinfunction "1_1") (pintype "passive"))
      (node (ref "R13") (pin "5") (pinfunction "R42_5") (pintype "bidirectional"))
      (node (ref "R13") (pin "6") (pinfunction "R32_6") (pintype "bidirectional"))
      (node (ref "R13") (pin "7") (pinfunction "R22_7") (pintype "bidirectional"))
      (node (ref "R13") (pin "8") (pinfunction "R12_8") (pintype "bidirectional"))
      (node (ref "R3") (pin "1") (pinfunction "1_1") (pintype "passive"))
      (node (ref "STONB") (pin "3") (pinfunction "3_3") (pintype "passive"))
      (node (ref "UART") (pin "3") (pinfunction "3_3") (pintype "passive"))
      (node (ref "ZMPPT1") (pin "2") (pinfunction "2_2") (pintype "passive"))
    )
    (net (code "25") (name "HVOUT") (class "Default")
      (node (ref "CHV") (pin "1") (pinfunction "1_1") (pintype "passive"))
      (node (ref "IC3") (pin "14") (pinfunction "HVOUT_14") (pintype "output"))
      (node (ref "R15") (pin "8") (pinfunction "R12_8") (pintype "bidirectional"))
    )
    (net (code "26") (name "LED") (class "Default")
      (node (ref "IC2") (pin "11") (pinfunction "PB1_11") (pintype "bidirectional"))
      (node (ref "R12") (pin "2") (pinfunction "2_2") (pintype "passive"))
    )
    (net (code "27") (name "LVOUT") (class "Default")
      (node (ref "CLV") (pin "1") (pinfunction "1_1") (pintype "passive"))
      (node (ref "IC3") (pin "11") (pinfunction "LVOUT_11") (pintype "output"))
      (node (ref "R14") (pin "6") (pinfunction "R32_6") (pintype "bidirectional"))
      (node (ref "SJ1") (pin "1") (pinfunction "1_1") (pintype "passive"))
    )
    (net (code "28") (name "NRST") (class "Default")
      (node (ref "DEBUG") (pin "10") (pinfunction "~{RESET}_10") (pintype "bidirectional"))
      (node (ref "IC2") (pin "3") (pinfunction "NRST_3") (pintype "bidirectional"))
    )
    (net (code "29") (name "Net-(C2-Pad1)") (class "Default")
      (node (ref "C2") (pin "1") (pinfunction "1_1") (pintype "passive"))
      (node (ref "L2") (pin "1") (pinfunction "1_1") (pintype "passive"))
      (node (ref "Z2") (pin "2") (pinfunction "2_2") (pintype "passive"))
    )
    (net (code "30") (name "Net-(C4-Pad1)") (class "Default")
      (node (ref "C4") (pin "1") (pinfunction "1_1") (pintype "passive"))
      (node (ref "L4") (pin "1") (pinfunction "1_1") (pintype "passive"))
      (node (ref "Z2") (pin "1") (pinfunction "1_1") (pintype "passive"))
    )
    (net (code "31") (name "Net-(C7-P$2)") (class "Default")
      (node (ref "C7") (pin "2") (pinfunction "P$2_2") (pintype "passive"))
      (node (ref "D2") (pin "3") (pinfunction "AC_3") (pintype "passive"))
    )
    (net (code "32") (name "Net-(C8-P$1)") (class "Default")
      (node (ref "C8") (pin "1") (pinfunction "P$1_1") (pintype "passive"))
      (node (ref "C9") (pin "1") (pinfunction "P$1_1") (pintype "passive"))
      (node (ref "D2") (pin "2") (pinfunction "C_2") (pintype "passive"))
      (node (ref "R9") (pin "1") (pinfunction "1_1") (pintype "passive"))
    )
    (net (code "33") (name "Net-(C10-P$1)") (class "Default")
      (node (ref "C10") (pin "1") (pinfunction "P$1_1") (pintype "passive"))
      (node (ref "IC1") (pin "4") (pinfunction "V-_4") (pintype "bidirectional"))
      (node (ref "R10") (pin "2") (pinfunction "2_2") (pintype "passive"))
      (node (ref "R11") (pin "2") (pinfunction "2_2") (pintype "passive"))
    )
    (net (code "34") (name "Net-(IC2-PA9)") (class "Default")
      (node (ref "IC2") (pin "14") (pinfunction "PA9_14") (pintype "bidirectional"))
      (node (ref "Q7") (pin "2") (pinfunction "S_2") (pintype "passive"))
    )
    (net (code "35") (name "Net-(IC2-PB9)") (class "Default")
      (node (ref "IC2") (pin "20") (pinfunction "PB9_20") (pintype "bidirectional"))
      (node (ref "R3") (pin "2") (pinfunction "2_2") (pintype "passive"))
    )
    (net (code "36") (name "Net-(IC3-SRC)") (class "Default")
      (node (ref "IC3") (pin "26") (pinfunction "SRC_26") (pintype "input"))
      (node (ref "NC") (pin "1") (pinfunction "1_1") (pintype "passive"))
    )
    (net (code "37") (name "Net-(IC3-SWBUCK)") (class "Default")
      (node (ref "IC3") (pin "2") (pinfunction "SWBUCK_2") (pintype "bidirectional"))
      (node (ref "LBUCK") (pin "1") (pinfunction "1_1") (pintype "passive"))
    )
    (net (code "38") (name "Net-(L2-Pad2)") (class "Default")
      (node (ref "L2") (pin "2") (pinfunction "2_2") (pintype "passive"))
      (node (ref "Z1") (pin "1") (pinfunction "1_1") (pintype "passive"))
    )
    (net (code "39") (name "Net-(L4-Pad2)") (class "Default")
      (node (ref "L4") (pin "2") (pinfunction "2_2") (pintype "passive"))
      (node (ref "Z3") (pin "1") (pinfunction "1_1") (pintype "passive"))
    )
    (net (code "40") (name "Net-(LED1-PadA)") (class "Default")
      (node (ref "LED1") (pin "A") (pinfunction "A_A") (pintype "passive"))
      (node (ref "R12") (pin "1") (pinfunction "1_1") (pintype "passive"))
    )
    (net (code "41") (name "REDRM") (class "Default")
      (node (ref "IC3") (pin "24") (pinfunction "REDRM_24") (pintype "bidirectional"))
      (node (ref "Z3") (pin "2") (pinfunction "2_2") (pintype "passive"))
    )
    (net (code "42") (name "REDRP") (class "Default")
      (node (ref "IC3") (pin "23") (pinfunction "REDRP_23") (pintype "bidirectional"))
      (node (ref "Z1") (pin "2") (pinfunction "2_2") (pintype "passive"))
    )
    (net (code "43") (name "RX") (class "Default")
      (node (ref "IC1") (pin "1") (pinfunction "OUT_1") (pintype "bidirectional"))
      (node (ref "IC2") (pin "6") (pinfunction "PA1_6") (pintype "bidirectional"))
    )
    (net (code "44") (name "RX_BITLINE") (class "Default")
      (node (ref "C9") (pin "2") (pinfunction "P$2_2") (pintype "passive"))
      (node (ref "IC1") (pin "3") (pinfunction "V+_3") (pintype "bidirectional"))
      (node (ref "R10") (pin "1") (pinfunction "1_1") (pintype "passive"))
      (node (ref "R9") (pin "2") (pinfunction "2_2") (pintype "passive"))
    )
    (net (code "45") (name "RX_EN") (class "Default")
      (node (ref "C11") (pin "1") (pinfunction "P$1_1") (pintype "passive"))
      (node (ref "IC1") (pin "5") (pinfunction "VCC_5") (pintype "bidirectional"))
      (node (ref "IC2") (pin "5") (pinfunction "PA0_5") (pintype "bidirectional"))
    )
    (net (code "46") (name "S1") (class "Default")
      (node (ref "C1") (pin "1") (pinfunction "1_1") (pintype "passive"))
      (node (ref "C2") (pin "2") (pinfunction "2_2") (pintype "passive"))
      (node (ref "L1") (pin "2") (pinfunction "2_2") (pintype "passive"))
      (node (ref "SJ2") (pin "3") (pinfunction "3_3") (pintype "passive"))
    )
    (net (code "47") (name "S2") (class "Default")
      (node (ref "C3") (pin "1") (pinfunction "1_1") (pintype "passive"))
      (node (ref "C4") (pin "2") (pinfunction "2_2") (pintype "passive"))
      (node (ref "L3") (pin "2") (pinfunction "2_2") (pintype "passive"))
      (node (ref "SJ2") (pin "1") (pinfunction "1_1") (pintype "passive"))
    )
    (net (code "48") (name "SCL") (class "Default")
      (node (ref "AUX") (pin "4") (pinfunction "4_4") (pintype "passive"))
      (node (ref "IC2") (pin "7") (pinfunction "PA4_7") (pintype "bidirectional"))
    )
    (net (code "49") (name "SDA") (class "Default")
      (node (ref "AUX") (pin "3") (pinfunction "3_3") (pintype "passive"))
      (node (ref "IC2") (pin "15") (pinfunction "PA10_15") (pintype "bidirectional"))
    )
    (net (code "50") (name "SELMPP0") (class "Default")
      (node (ref "IC3") (pin "8") (pinfunction "SELMPP0_8") (pintype "input"))
      (node (ref "MPP0") (pin "2") (pinfunction "2_2") (pintype "passive"))
    )
    (net (code "51") (name "SELMPP1") (class "Default")
      (node (ref "IC3") (pin "7") (pinfunction "SELMPP1_7") (pintype "input"))
      (node (ref "MPP1") (pin "2") (pinfunction "2_2") (pintype "passive"))
    )
    (net (code "52") (name "SIGNAL") (class "Default")
      (node (ref "C7") (pin "1") (pinfunction "P$1_1") (pintype "passive"))
      (node (ref "L5") (pin "2") (pinfunction "2_2") (pintype "passive"))
      (node (ref "SJ2") (pin "2") (pinfunction "2_2") (pintype "passive"))
    )
    (net (code "53") (name "STAT0") (class "Default")
      (node (ref "IC2") (pin "8") (pinfunction "PA5_8") (pintype "bidirectional"))
      (node (ref "IC3") (pin "21") (pinfunction "STATUS0_21") (pintype "output"))
    )
    (net (code "54") (name "STAT1") (class "Default")
      (node (ref "IC2") (pin "9") (pinfunction "PA6_9") (pintype "bidirectional"))
      (node (ref "IC3") (pin "20") (pinfunction "STATUS1_20") (pintype "output"))
    )
    (net (code "55") (name "STAT2") (class "Default")
      (node (ref "IC2") (pin "10") (pinfunction "PA7_10") (pintype "bidirectional"))
      (node (ref "IC3") (pin "19") (pinfunction "STATUS2_19") (pintype "output"))
    )
    (net (code "56") (name "STONBAT") (class "Default")
      (node (ref "IC3") (pin "13") (pinfunction "STONBATT_13") (pintype "input"))
      (node (ref "STONB") (pin "2") (pinfunction "2_2") (pintype "passive"))
    )
    (net (code "57") (name "SWBOOST") (class "Default")
      (node (ref "IC3") (pin "28") (pinfunction "SWBOOST_28") (pintype "bidirectional"))
      (node (ref "LBOOST") (pin "1") (pinfunction "1_1") (pintype "passive"))
    )
    (net (code "58") (name "SWDCLK") (class "Default")
      (node (ref "DEBUG") (pin "4") (pinfunction "SWDCLK/TCK_4") (pintype "bidirectional"))
      (node (ref "IC2") (pin "17") (pinfunction "PA14_17") (pintype "bidirectional"))
    )
    (net (code "59") (name "SWDIO") (class "Default")
      (node (ref "DEBUG") (pin "2") (pinfunction "SWDIO/TMS_2") (pintype "bidirectional"))
      (node (ref "IC2") (pin "16") (pinfunction "PA13_16") (pintype "bidirectional"))
    )
    (net (code "60") (name "TX") (class "Default")
      (node (ref "IC4") (pin "2") (pinfunction "CTRL_2") (pintype "passive"))
      (node (ref "Q7") (pin "3") (pinfunction "D_3") (pintype "passive"))
    )
    (net (code "61") (name "USART2_RX") (class "Default")
      (node (ref "IC2") (pin "19") (pinfunction "PB7_19") (pintype "bidirectional"))
      (node (ref "UART") (pin "1") (pinfunction "1_1") (pintype "passive"))
    )
    (net (code "62") (name "USART2_TX") (class "Default")
      (node (ref "IC2") (pin "18") (pinfunction "PB6_18") (pintype "bidirectional"))
      (node (ref "Q7") (pin "1") (pinfunction "G_1") (pintype "passive"))
      (node (ref "UART") (pin "2") (pinfunction "2_2") (pintype "passive"))
    )
    (net (code "63") (name "VDD") (class "Default")
      (node (ref "C12") (pin "1") (pinfunction "P$1_1") (pintype "passive"))
      (node (ref "C13") (pin "1") (pinfunction "P$1_1") (pintype "passive"))
      (node (ref "IC2") (pin "13") (pinfunction "VDD_13") (pintype "bidirectional"))
      (node (ref "IC2") (pin "4") (pinfunction "VDDA_4") (pintype "bidirectional"))
      (node (ref "IC4") (pin "1") (pinfunction "VDD_1") (pintype "power_in"))
      (node (ref "LS4") (pin "3") (pinfunction "VIN_3") (pintype "input"))
      (node (ref "SJ1") (pin "2") (pinfunction "2_2") (pintype "passive"))
    )
    (net (code "64") (name "VDD-AUX") (class "Default")
      (node (ref "AUX") (pin "1") (pinfunction "1_1") (pintype "passive"))
      (node (ref "LS4") (pin "1") (pinfunction "VOUT_1") (pintype "output"))
    )
    (net (code "65") (name "VDD-AUX-EN") (class "Default")
      (node (ref "AUX") (pin "2") (pinfunction "2_2") (pintype "passive"))
      (node (ref "IC2") (pin "1") (pinfunction "PC14_1") (pintype "bidirectional"))
      (node (ref "LS4") (pin "4") (pinfunction "EN_4") (pintype "input"))
    )
    (net (code "66") (name "ZMPP") (class "Default")
      (node (ref "IC3") (pin "25") (pinfunction "ZMPP_25") (pintype "bidirectional"))
      (node (ref "ZMPPT1") (pin "1") (pinfunction "1_1") (pintype "passive"))
    )
    (net (code "67") (name "unconnected-(DEBUG-KEY-Pad7)") (class "Default")
      (node (ref "DEBUG") (pin "7") (pinfunction "KEY_7") (pintype "bidirectional"))
    )
    (net (code "68") (name "unconnected-(DEBUG-NC{slash}TDI-Pad8)") (class "Default")
      (node (ref "DEBUG") (pin "8") (pinfunction "NC/TDI_8") (pintype "bidirectional"))
    )
    (net (code "69") (name "unconnected-(DEBUG-SWO{slash}TDO-Pad6)") (class "Default")
      (node (ref "DEBUG") (pin "6") (pinfunction "SWO/TDO_6") (pintype "bidirectional"))
    )
    (net (code "70") (name "unconnected-(DISCHARGE-Pad7)") (class "Default")
      (node (ref "DISCHARGE") (pin "7") (pinfunction "7_7") (pintype "passive"))
    )
    (net (code "71") (name "unconnected-(DISCHARGE-Pad8)") (class "Default")
      (node (ref "DISCHARGE") (pin "8") (pinfunction "8_8") (pintype "passive"))
    )
    (net (code "72") (name "unconnected-(DISCHARGE-Pad9)") (class "Default")
      (node (ref "DISCHARGE") (pin "9") (pinfunction "9_9") (pintype "passive"))
    )
    (net (code "73") (name "unconnected-(IC2-PC15-Pad2)") (class "Default")
      (node (ref "IC2") (pin "2") (pinfunction "PC15_2") (pintype "bidirectional"))
    )
    (net (code "74") (name "unconnected-(R13-R31-Pad3)") (class "Default")
      (node (ref "R13") (pin "3") (pinfunction "R31_3") (pintype "bidirectional"))
    )
    (net (code "75") (name "unconnected-(R13-R41-Pad4)") (class "Default")
      (node (ref "R13") (pin "4") (pinfunction "R41_4") (pintype "bidirectional"))
    )
    (net (code "76") (name "unconnected-(R15-R31-Pad3)") (class "Default")
      (node (ref "R15") (pin "3") (pinfunction "R31_3") (pintype "bidirectional"))
    )
    (net (code "77") (name "unconnected-(R15-R32-Pad6)") (class "Default")
      (node (ref "R15") (pin "6") (pinfunction "R32_6") (pintype "bidirectional"))
    )
    (net (code "78") (name "unconnected-(R15-R41-Pad4)") (class "Default")
      (node (ref "R15") (pin "4") (pinfunction "R41_4") (pintype "bidirectional"))
    )
    (net (code "79") (name "unconnected-(R15-R42-Pad5)") (class "Default")
      (node (ref "R15") (pin "5") (pinfunction "R42_5") (pintype "bidirectional"))
    )
  )
)
